# with_solar_universal.net
KiCad netlist of a schematic drawn in EAGLE
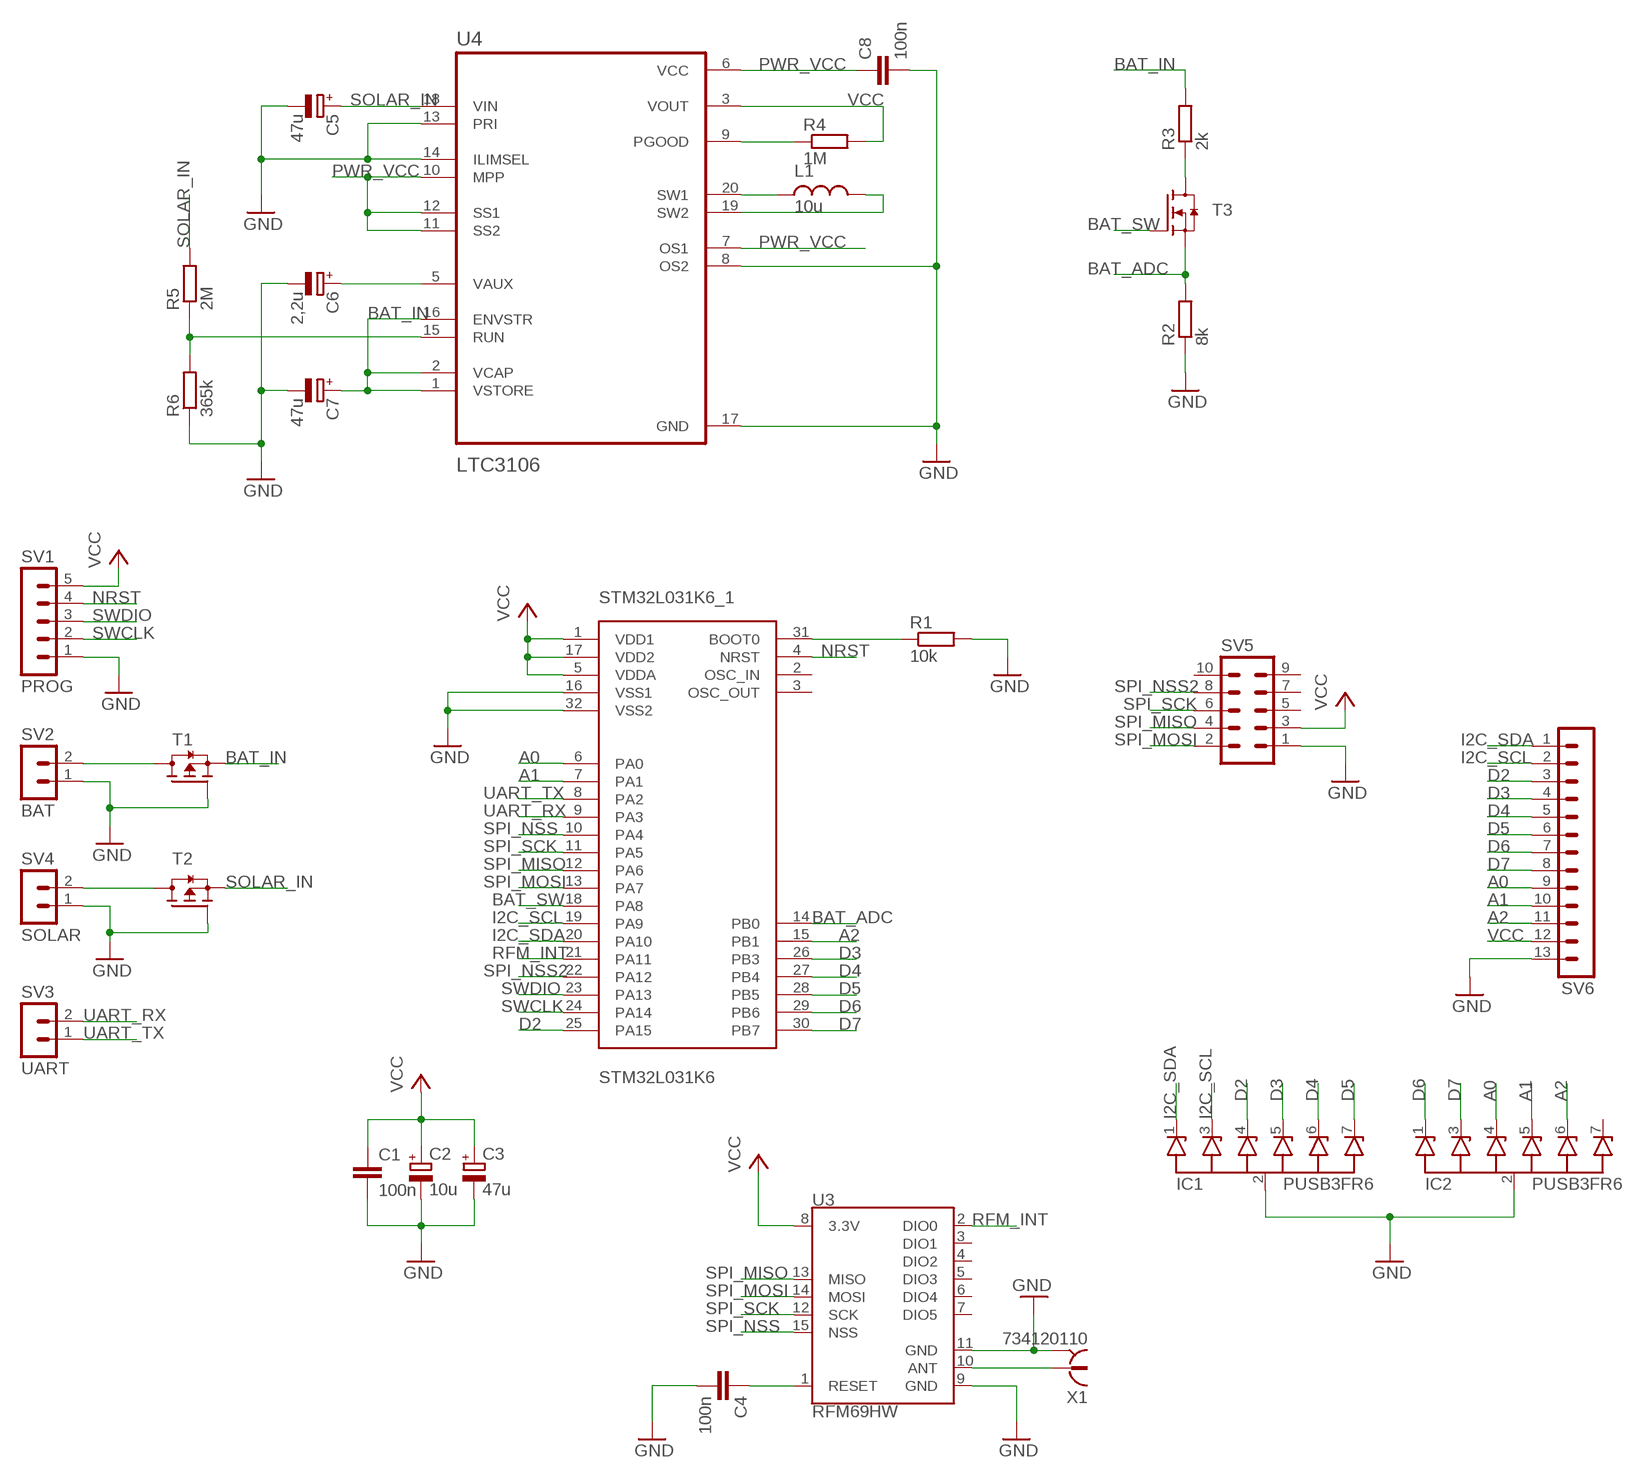
[diagram p0: schematic, sheet 1]

(export (version "E")
  (design (tool "Eeschema 10.0.6"))
  (components
    (comp (ref "C1")
      (value "100n")
      (footprint "eagle-import:C1206")
      (libsource (lib "eagle-import") (part "C-EUC1206"))
    )
    (comp (ref "C2")
      (value "10u")
      (footprint "eagle-import:UD-4X5,8_NICHICON")
      (libsource (lib "eagle-import") (part "CPOL-EUUD-4X5,8"))
    )
    (comp (ref "C3")
      (value "47u")
      (footprint "eagle-import:UD-4X5,8_NICHICON")
      (libsource (lib "eagle-import") (part "CPOL-EUUD-4X5,8"))
    )
    (comp (ref "C4")
      (value "100n")
      (footprint "eagle-import:C1206")
      (libsource (lib "eagle-import") (part "C-EUC1206"))
    )
    (comp (ref "C5")
      (value "47u")
      (footprint "eagle-import:UD-4X5,8_NICHICON")
      (libsource (lib "eagle-import") (part "CPOL-EUUD-4X5,8"))
    )
    (comp (ref "C6")
      (value "2,2u")
      (footprint "eagle-import:UD-4X5,8_NICHICON")
      (libsource (lib "eagle-import") (part "CPOL-EUUD-4X5,8"))
    )
    (comp (ref "C7")
      (value "47u")
      (footprint "eagle-import:UD-4X5,8_NICHICON")
      (libsource (lib "eagle-import") (part "CPOL-EUUD-4X5,8"))
    )
    (comp (ref "C8")
      (value "100n")
      (footprint "eagle-import:C1206")
      (libsource (lib "eagle-import") (part "C-EUC1206"))
    )
    (comp (ref "IC1")
      (value "PUSB3FR6")
      (footprint "eagle-import:DFN2111-7")
      (libsource (lib "eagle-import") (part "PUSB3FR6"))
    )
    (comp (ref "IC2")
      (value "PUSB3FR6")
      (footprint "eagle-import:DFN2111-7")
      (libsource (lib "eagle-import") (part "PUSB3FR6"))
    )
    (comp (ref "L1")
      (value "10u")
      (footprint "eagle-import:R1210")
      (libsource (lib "eagle-import") (part "L1210"))
    )
    (comp (ref "R1")
      (value "10k")
      (footprint "eagle-import:R0805")
      (libsource (lib "eagle-import") (part "R-EU_R0805"))
    )
    (comp (ref "R2")
      (value "8k")
      (footprint "eagle-import:R0805")
      (libsource (lib "eagle-import") (part "R-EU_R0805"))
    )
    (comp (ref "R3")
      (value "2k")
      (footprint "eagle-import:R0805")
      (libsource (lib "eagle-import") (part "R-EU_R0805"))
    )
    (comp (ref "R4")
      (value "1M")
      (footprint "eagle-import:R0805")
      (libsource (lib "eagle-import") (part "R-EU_R0805"))
    )
    (comp (ref "R5")
      (value "2M")
      (footprint "eagle-import:R0805")
      (libsource (lib "eagle-import") (part "R-EU_R0805"))
    )
    (comp (ref "R6")
      (value "365k")
      (footprint "eagle-import:R0805")
      (libsource (lib "eagle-import") (part "R-EU_R0805"))
    )
    (comp (ref "STM32L031K6_1")
      (value "STM32L031K6")
      (footprint "eagle-import:LQFP32-7X7")
      (libsource (lib "eagle-import") (part "STM32L031K6"))
    )
    (comp (ref "SV1")
      (value "PROG")
      (footprint "eagle-import:MA05-1")
      (libsource (lib "eagle-import") (part "MA05-1"))
    )
    (comp (ref "SV2")
      (value "BAT")
      (footprint "eagle-import:MA02-1")
      (libsource (lib "eagle-import") (part "MA02-1"))
    )
    (comp (ref "SV3")
      (value "UART")
      (footprint "eagle-import:MA02-1")
      (libsource (lib "eagle-import") (part "MA02-1"))
    )
    (comp (ref "SV4")
      (value "SOLAR")
      (footprint "eagle-import:MA02-1")
      (libsource (lib "eagle-import") (part "MA02-1"))
    )
    (comp (ref "SV5")
      (value "MA05-2")
      (footprint "eagle-import:MA05-2")
      (libsource (lib "eagle-import") (part "MA05-2"))
    )
    (comp (ref "SV6")
      (value "MA13-1")
      (footprint "eagle-import:MA13-1")
      (libsource (lib "eagle-import") (part "MA13-1"))
    )
    (comp (ref "T1")
      (value "RTQ035P02HZG")
      (footprint "eagle-import:SOT457R_PHILIPS")
      (libsource (lib "eagle-import") (part "RTQ035P02HZG"))
    )
    (comp (ref "T2")
      (value "RTQ035P02HZG")
      (footprint "eagle-import:SOT457R_PHILIPS")
      (libsource (lib "eagle-import") (part "RTQ035P02HZG"))
    )
    (comp (ref "T3")
      (value "RQ6E050AJTCR")
      (footprint "eagle-import:SOT457R_PHILIPS")
      (libsource (lib "eagle-import") (part "RQ6E050AJTCR"))
    )
    (comp (ref "U3")
      (value "RFM69HW")
      (footprint "eagle-import:RFM69W-XXXS2")
      (libsource (lib "eagle-import") (part "RFM69HW"))
    )
    (comp (ref "U4")
      (value "LTC3106")
      (footprint "eagle-import:LTC3106")
      (libsource (lib "eagle-import") (part "LTC3106"))
    )
    (comp (ref "X1")
      (value "734120110")
      (footprint "eagle-import:734120110")
      (libsource (lib "eagle-import") (part "734120110"))
    )
  )
  (nets
    (net (code "1") (name "/A0") (class "Default")
      (node (ref "IC2") (pin "4") (pinfunction "4_4") (pintype "bidirectional"))
      (node (ref "STM32L031K6_1") (pin "6") (pinfunction "PA0_6") (pintype "bidirectional"))
      (node (ref "SV6") (pin "9") (pinfunction "9_9") (pintype "passive"))
    )
    (net (code "2") (name "/A1") (class "Default")
      (node (ref "IC2") (pin "5") (pinfunction "5_5") (pintype "bidirectional"))
      (node (ref "STM32L031K6_1") (pin "7") (pinfunction "PA1_7") (pintype "bidirectional"))
      (node (ref "SV6") (pin "10") (pinfunction "10_10") (pintype "passive"))
    )
    (net (code "3") (name "/A2") (class "Default")
      (node (ref "IC2") (pin "6") (pinfunction "6_6") (pintype "bidirectional"))
      (node (ref "STM32L031K6_1") (pin "15") (pinfunction "PB1_15") (pintype "bidirectional"))
      (node (ref "SV6") (pin "11") (pinfunction "11_11") (pintype "passive"))
    )
    (net (code "4") (name "/BAT_ADC") (class "Default")
      (node (ref "R2") (pin "2") (pinfunction "2_2") (pintype "passive"))
      (node (ref "STM32L031K6_1") (pin "14") (pinfunction "PB0_14") (pintype "bidirectional"))
      (node (ref "T3") (pin "4") (pinfunction "S_4") (pintype "passive"))
    )
    (net (code "5") (name "/BAT_IN") (class "Default")
      (node (ref "C7") (pin "+") (pinfunction "+_+") (pintype "passive"))
      (node (ref "R3") (pin "2") (pinfunction "2_2") (pintype "passive"))
      (node (ref "T1") (pin "4") (pinfunction "S_4") (pintype "passive"))
      (node (ref "U4") (pin "1") (pinfunction "VSTORE_1") (pintype "bidirectional"))
      (node (ref "U4") (pin "16") (pinfunction "ENVSTR_16") (pintype "input"))
      (node (ref "U4") (pin "2") (pinfunction "VCAP_2") (pintype "bidirectional"))
    )
    (net (code "6") (name "/BAT_SW") (class "Default")
      (node (ref "STM32L031K6_1") (pin "18") (pinfunction "PA8_18") (pintype "bidirectional"))
      (node (ref "T3") (pin "3") (pinfunction "G_3") (pintype "passive"))
    )
    (net (code "7") (name "/D2") (class "Default")
      (node (ref "IC1") (pin "4") (pinfunction "4_4") (pintype "bidirectional"))
      (node (ref "STM32L031K6_1") (pin "25") (pinfunction "PA15_25") (pintype "bidirectional"))
      (node (ref "SV6") (pin "3") (pinfunction "3_3") (pintype "passive"))
    )
    (net (code "8") (name "/D3") (class "Default")
      (node (ref "IC1") (pin "5") (pinfunction "5_5") (pintype "bidirectional"))
      (node (ref "STM32L031K6_1") (pin "26") (pinfunction "PB3_26") (pintype "bidirectional"))
      (node (ref "SV6") (pin "4") (pinfunction "4_4") (pintype "passive"))
    )
    (net (code "9") (name "/D4") (class "Default")
      (node (ref "IC1") (pin "6") (pinfunction "6_6") (pintype "bidirectional"))
      (node (ref "STM32L031K6_1") (pin "27") (pinfunction "PB4_27") (pintype "bidirectional"))
      (node (ref "SV6") (pin "5") (pinfunction "5_5") (pintype "passive"))
    )
    (net (code "10") (name "/D5") (class "Default")
      (node (ref "IC1") (pin "7") (pinfunction "7_7") (pintype "bidirectional"))
      (node (ref "STM32L031K6_1") (pin "28") (pinfunction "PB5_28") (pintype "bidirectional"))
      (node (ref "SV6") (pin "6") (pinfunction "6_6") (pintype "passive"))
    )
    (net (code "11") (name "/D6") (class "Default")
      (node (ref "IC2") (pin "1") (pinfunction "1_1") (pintype "bidirectional"))
      (node (ref "STM32L031K6_1") (pin "29") (pinfunction "PB6_29") (pintype "bidirectional"))
      (node (ref "SV6") (pin "7") (pinfunction "7_7") (pintype "passive"))
    )
    (net (code "12") (name "/D7") (class "Default")
      (node (ref "IC2") (pin "3") (pinfunction "3_3") (pintype "bidirectional"))
      (node (ref "STM32L031K6_1") (pin "30") (pinfunction "PB7_30") (pintype "bidirectional"))
      (node (ref "SV6") (pin "8") (pinfunction "8_8") (pintype "passive"))
    )
    (net (code "13") (name "/I2C_SCL") (class "Default")
      (node (ref "IC1") (pin "3") (pinfunction "3_3") (pintype "bidirectional"))
      (node (ref "STM32L031K6_1") (pin "19") (pinfunction "PA9_19") (pintype "bidirectional"))
      (node (ref "SV6") (pin "2") (pinfunction "2_2") (pintype "passive"))
    )
    (net (code "14") (name "/I2C_SDA") (class "Default")
      (node (ref "IC1") (pin "1") (pinfunction "1_1") (pintype "bidirectional"))
      (node (ref "STM32L031K6_1") (pin "20") (pinfunction "PA10_20") (pintype "bidirectional"))
      (node (ref "SV6") (pin "1") (pinfunction "1_1") (pintype "passive"))
    )
    (net (code "15") (name "/NRST") (class "Default")
      (node (ref "STM32L031K6_1") (pin "4") (pinfunction "NRST_4") (pintype "bidirectional"))
      (node (ref "SV1") (pin "4") (pinfunction "4_4") (pintype "passive"))
    )
    (net (code "16") (name "/PWR_VCC") (class "Default")
      (node (ref "C8") (pin "1") (pinfunction "1_1") (pintype "passive"))
      (node (ref "U4") (pin "10") (pinfunction "MPP_10") (pintype "input"))
      (node (ref "U4") (pin "11") (pinfunction "SS2_11") (pintype "input"))
      (node (ref "U4") (pin "12") (pinfunction "SS1_12") (pintype "input"))
      (node (ref "U4") (pin "6") (pinfunction "VCC_6") (pintype "power_in"))
      (node (ref "U4") (pin "7") (pinfunction "OS1_7") (pintype "input"))
    )
    (net (code "17") (name "/RFM_INT") (class "Default")
      (node (ref "STM32L031K6_1") (pin "21") (pinfunction "PA11_21") (pintype "bidirectional"))
      (node (ref "U3") (pin "2") (pinfunction "DIO0_2") (pintype "bidirectional"))
    )
    (net (code "18") (name "/SOLAR_IN") (class "Default")
      (node (ref "C5") (pin "+") (pinfunction "+_+") (pintype "passive"))
      (node (ref "R5") (pin "2") (pinfunction "2_2") (pintype "passive"))
      (node (ref "T2") (pin "4") (pinfunction "S_4") (pintype "passive"))
      (node (ref "U4") (pin "18") (pinfunction "VIN_18") (pintype "input"))
    )
    (net (code "19") (name "/SPI_MISO") (class "Default")
      (node (ref "STM32L031K6_1") (pin "12") (pinfunction "PA6_12") (pintype "bidirectional"))
      (node (ref "SV5") (pin "4") (pinfunction "4_4") (pintype "passive"))
      (node (ref "U3") (pin "13") (pinfunction "MISO_13") (pintype "bidirectional"))
    )
    (net (code "20") (name "/SPI_MOSI") (class "Default")
      (node (ref "STM32L031K6_1") (pin "13") (pinfunction "PA7_13") (pintype "bidirectional"))
      (node (ref "SV5") (pin "2") (pinfunction "2_2") (pintype "passive"))
      (node (ref "U3") (pin "14") (pinfunction "MOSI_14") (pintype "input"))
    )
    (net (code "21") (name "/SPI_NSS") (class "Default")
      (node (ref "STM32L031K6_1") (pin "10") (pinfunction "PA4_10") (pintype "bidirectional"))
      (node (ref "U3") (pin "15") (pinfunction "NSS_15") (pintype "input"))
    )
    (net (code "22") (name "/SPI_NSS2") (class "Default")
      (node (ref "STM32L031K6_1") (pin "22") (pinfunction "PA12_22") (pintype "bidirectional"))
      (node (ref "SV5") (pin "8") (pinfunction "8_8") (pintype "passive"))
    )
    (net (code "23") (name "/SPI_SCK") (class "Default")
      (node (ref "STM32L031K6_1") (pin "11") (pinfunction "PA5_11") (pintype "bidirectional"))
      (node (ref "SV5") (pin "6") (pinfunction "6_6") (pintype "passive"))
      (node (ref "U3") (pin "12") (pinfunction "SCK_12") (pintype "input"))
    )
    (net (code "24") (name "/SWCLK") (class "Default")
      (node (ref "STM32L031K6_1") (pin "24") (pinfunction "PA14_24") (pintype "bidirectional"))
      (node (ref "SV1") (pin "2") (pinfunction "2_2") (pintype "passive"))
    )
    (net (code "25") (name "/SWDIO") (class "Default")
      (node (ref "STM32L031K6_1") (pin "23") (pinfunction "PA13_23") (pintype "bidirectional"))
      (node (ref "SV1") (pin "3") (pinfunction "3_3") (pintype "passive"))
    )
    (net (code "26") (name "/UART_RX") (class "Default")
      (node (ref "STM32L031K6_1") (pin "9") (pinfunction "PA3_9") (pintype "bidirectional"))
      (node (ref "SV3") (pin "2") (pinfunction "3_2") (pintype "passive"))
    )
    (net (code "27") (name "/UART_TX") (class "Default")
      (node (ref "STM32L031K6_1") (pin "8") (pinfunction "PA2_8") (pintype "bidirectional"))
      (node (ref "SV3") (pin "1") (pinfunction "2_1") (pintype "passive"))
    )
    (net (code "28") (name "GND") (class "Default")
      (node (ref "C1") (pin "2") (pinfunction "2_2") (pintype "passive"))
      (node (ref "C2") (pin "-") (pinfunction "-_-") (pintype "passive"))
      (node (ref "C3") (pin "-") (pinfunction "-_-") (pintype "passive"))
      (node (ref "C4") (pin "2") (pinfunction "2_2") (pintype "passive"))
      (node (ref "C5") (pin "-") (pinfunction "-_-") (pintype "passive"))
      (node (ref "C6") (pin "-") (pinfunction "-_-") (pintype "passive"))
      (node (ref "C7") (pin "-") (pinfunction "-_-") (pintype "passive"))
      (node (ref "C8") (pin "2") (pinfunction "2_2") (pintype "passive"))
      (node (ref "IC1") (pin "2") (pinfunction "2_2") (pintype "power_in"))
      (node (ref "IC2") (pin "2") (pinfunction "2_2") (pintype "power_in"))
      (node (ref "R1") (pin "2") (pinfunction "2_2") (pintype "passive"))
      (node (ref "R2") (pin "1") (pinfunction "1_1") (pintype "passive"))
      (node (ref "R6") (pin "1") (pinfunction "1_1") (pintype "passive"))
      (node (ref "STM32L031K6_1") (pin "16") (pinfunction "VSS1_16") (pintype "bidirectional"))
      (node (ref "STM32L031K6_1") (pin "32") (pinfunction "VSS2_32") (pintype "bidirectional"))
      (node (ref "SV1") (pin "1") (pinfunction "1_1") (pintype "passive"))
      (node (ref "SV2") (pin "1") (pinfunction "2_1") (pintype "passive"))
      (node (ref "SV4") (pin "1") (pinfunction "2_1") (pintype "passive"))
      (node (ref "SV5") (pin "1") (pinfunction "1_1") (pintype "passive"))
      (node (ref "SV6") (pin "13") (pinfunction "13_13") (pintype "passive"))
      (node (ref "T1") (pin "3") (pinfunction "G_3") (pintype "passive"))
      (node (ref "T2") (pin "3") (pinfunction "G_3") (pintype "passive"))
      (node (ref "U3") (pin "11") (pinfunction "GND_11") (pintype "power_in"))
      (node (ref "U3") (pin "9") (pinfunction "GND_9") (pintype "power_in"))
      (node (ref "U4") (pin "13") (pinfunction "PRI_13") (pintype "input"))
      (node (ref "U4") (pin "14") (pinfunction "ILIMSEL_14") (pintype "input"))
      (node (ref "U4") (pin "17") (pinfunction "GND_17") (pintype "power_in"))
      (node (ref "U4") (pin "8") (pinfunction "OS2_8") (pintype "input"))
      (node (ref "X1") (pin "S@1") (pinfunction "2_S@1") (pintype "passive"))
      (node (ref "X1") (pin "S@2") (pinfunction "2_S@2") (pintype "passive"))
      (node (ref "X1") (pin "S@3") (pinfunction "2_S@3") (pintype "passive"))
    )
    (net (code "29") (name "Net-(R3-Pad1)") (class "Default")
      (node (ref "R3") (pin "1") (pinfunction "1_1") (pintype "passive"))
      (node (ref "T3") (pin "1") (pinfunction "D_1") (pintype "passive"))
      (node (ref "T3") (pin "2") (pinfunction "D_2") (pintype "passive"))
      (node (ref "T3") (pin "5") (pinfunction "D_5") (pintype "passive"))
      (node (ref "T3") (pin "6") (pinfunction "D_6") (pintype "passive"))
    )
    (net (code "30") (name "Net-(STM32L031K6_1-BOOT0)") (class "Default")
      (node (ref "R1") (pin "1") (pinfunction "1_1") (pintype "passive"))
      (node (ref "STM32L031K6_1") (pin "31") (pinfunction "BOOT0_31") (pintype "bidirectional"))
    )
    (net (code "31") (name "Net-(SV2-3)") (class "Default")
      (node (ref "SV2") (pin "2") (pinfunction "3_2") (pintype "passive"))
      (node (ref "T1") (pin "1") (pinfunction "D_1") (pintype "passive"))
      (node (ref "T1") (pin "2") (pinfunction "D_2") (pintype "passive"))
      (node (ref "T1") (pin "5") (pinfunction "D_5") (pintype "passive"))
      (node (ref "T1") (pin "6") (pinfunction "D_6") (pintype "passive"))
    )
    (net (code "32") (name "Net-(SV4-3)") (class "Default")
      (node (ref "SV4") (pin "2") (pinfunction "3_2") (pintype "passive"))
      (node (ref "T2") (pin "1") (pinfunction "D_1") (pintype "passive"))
      (node (ref "T2") (pin "2") (pinfunction "D_2") (pintype "passive"))
      (node (ref "T2") (pin "5") (pinfunction "D_5") (pintype "passive"))
      (node (ref "T2") (pin "6") (pinfunction "D_6") (pintype "passive"))
    )
    (net (code "33") (name "Net-(U3-ANT)") (class "Default")
      (node (ref "U3") (pin "10") (pinfunction "ANT_10") (pintype "passive"))
      (node (ref "X1") (pin "1") (pinfunction "1_1") (pintype "passive"))
    )
    (net (code "34") (name "Net-(U3-RESET)") (class "Default")
      (node (ref "C4") (pin "1") (pinfunction "1_1") (pintype "passive"))
      (node (ref "U3") (pin "1") (pinfunction "RESET_1") (pintype "input"))
    )
    (net (code "35") (name "Net-(U4-PGOOD)") (class "Default")
      (node (ref "R4") (pin "1") (pinfunction "1_1") (pintype "passive"))
      (node (ref "U4") (pin "9") (pinfunction "PGOOD_9") (pintype "bidirectional"))
    )
    (net (code "36") (name "Net-(U4-RUN)") (class "Default")
      (node (ref "R5") (pin "1") (pinfunction "1_1") (pintype "passive"))
      (node (ref "R6") (pin "2") (pinfunction "2_2") (pintype "passive"))
      (node (ref "U4") (pin "15") (pinfunction "RUN_15") (pintype "input"))
    )
    (net (code "37") (name "Net-(U4-SW1)") (class "Default")
      (node (ref "L1") (pin "1") (pinfunction "1_1") (pintype "passive"))
      (node (ref "U4") (pin "20") (pinfunction "SW1_20") (pintype "bidirectional"))
    )
    (net (code "38") (name "Net-(U4-SW2)") (class "Default")
      (node (ref "L1") (pin "2") (pinfunction "2_2") (pintype "passive"))
      (node (ref "U4") (pin "19") (pinfunction "SW2_19") (pintype "bidirectional"))
    )
    (net (code "39") (name "Net-(U4-VAUX)") (class "Default")
      (node (ref "C6") (pin "+") (pinfunction "+_+") (pintype "passive"))
      (node (ref "U4") (pin "5") (pinfunction "VAUX_5") (pintype "bidirectional"))
    )
    (net (code "40") (name "VCC") (class "Default")
      (node (ref "C1") (pin "1") (pinfunction "1_1") (pintype "passive"))
      (node (ref "C2") (pin "+") (pinfunction "+_+") (pintype "passive"))
      (node (ref "C3") (pin "+") (pinfunction "+_+") (pintype "passive"))
      (node (ref "R4") (pin "2") (pinfunction "2_2") (pintype "passive"))
      (node (ref "STM32L031K6_1") (pin "1") (pinfunction "VDD1_1") (pintype "bidirectional"))
      (node (ref "STM32L031K6_1") (pin "17") (pinfunction "VDD2_17") (pintype "bidirectional"))
      (node (ref "STM32L031K6_1") (pin "5") (pinfunction "VDDA_5") (pintype "bidirectional"))
      (node (ref "SV1") (pin "5") (pinfunction "5_5") (pintype "passive"))
      (node (ref "SV5") (pin "3") (pinfunction "3_3") (pintype "passive"))
      (node (ref "SV6") (pin "12") (pinfunction "12_12") (pintype "passive"))
      (node (ref "U3") (pin "8") (pinfunction "3.3V_8") (pintype "power_in"))
      (node (ref "U4") (pin "3") (pinfunction "VOUT_3") (pintype "output"))
    )
    (net (code "41") (name "unconnected-(IC2-Pad7)") (class "Default")
      (node (ref "IC2") (pin "7") (pinfunction "7_7") (pintype "bidirectional"))
    )
    (net (code "42") (name "unconnected-(STM32L031K6_1-OSC_IN-Pad2)") (class "Default")
      (node (ref "STM32L031K6_1") (pin "2") (pinfunction "OSC_IN_2") (pintype "bidirectional"))
    )
    (net (code "43") (name "unconnected-(STM32L031K6_1-OSC_OUT-Pad3)") (class "Default")
      (node (ref "STM32L031K6_1") (pin "3") (pinfunction "OSC_OUT_3") (pintype "bidirectional"))
    )
    (net (code "44") (name "unconnected-(SV5-Pad5)") (class "Default")
      (node (ref "SV5") (pin "5") (pinfunction "5_5") (pintype "passive"))
    )
    (net (code "45") (name "unconnected-(SV5-Pad7)") (class "Default")
      (node (ref "SV5") (pin "7") (pinfunction "7_7") (pintype "passive"))
    )
    (net (code "46") (name "unconnected-(SV5-Pad9)") (class "Default")
      (node (ref "SV5") (pin "9") (pinfunction "9_9") (pintype "passive"))
    )
    (net (code "47") (name "unconnected-(SV5-Pad10)") (class "Default")
      (node (ref "SV5") (pin "10") (pinfunction "10_10") (pintype "passive"))
    )
    (net (code "48") (name "unconnected-(U3-DIO1-Pad3)") (class "Default")
      (node (ref "U3") (pin "3") (pinfunction "DIO1_3") (pintype "bidirectional"))
    )
    (net (code "49") (name "unconnected-(U3-DIO2-Pad4)") (class "Default")
      (node (ref "U3") (pin "4") (pinfunction "DIO2_4") (pintype "bidirectional"))
    )
    (net (code "50") (name "unconnected-(U3-DIO3-Pad5)") (class "Default")
      (node (ref "U3") (pin "5") (pinfunction "DIO3_5") (pintype "bidirectional"))
    )
    (net (code "51") (name "unconnected-(U3-DIO4-Pad6)") (class "Default")
      (node (ref "U3") (pin "6") (pinfunction "DIO4_6") (pintype "bidirectional"))
    )
    (net (code "52") (name "unconnected-(U3-DIO5-Pad7)") (class "Default")
      (node (ref "U3") (pin "7") (pinfunction "DIO5_7") (pintype "bidirectional"))
    )
  )
)
